# MOSFET_drivers.net
KiCad netlist of a schematic drawn in Altium Designer
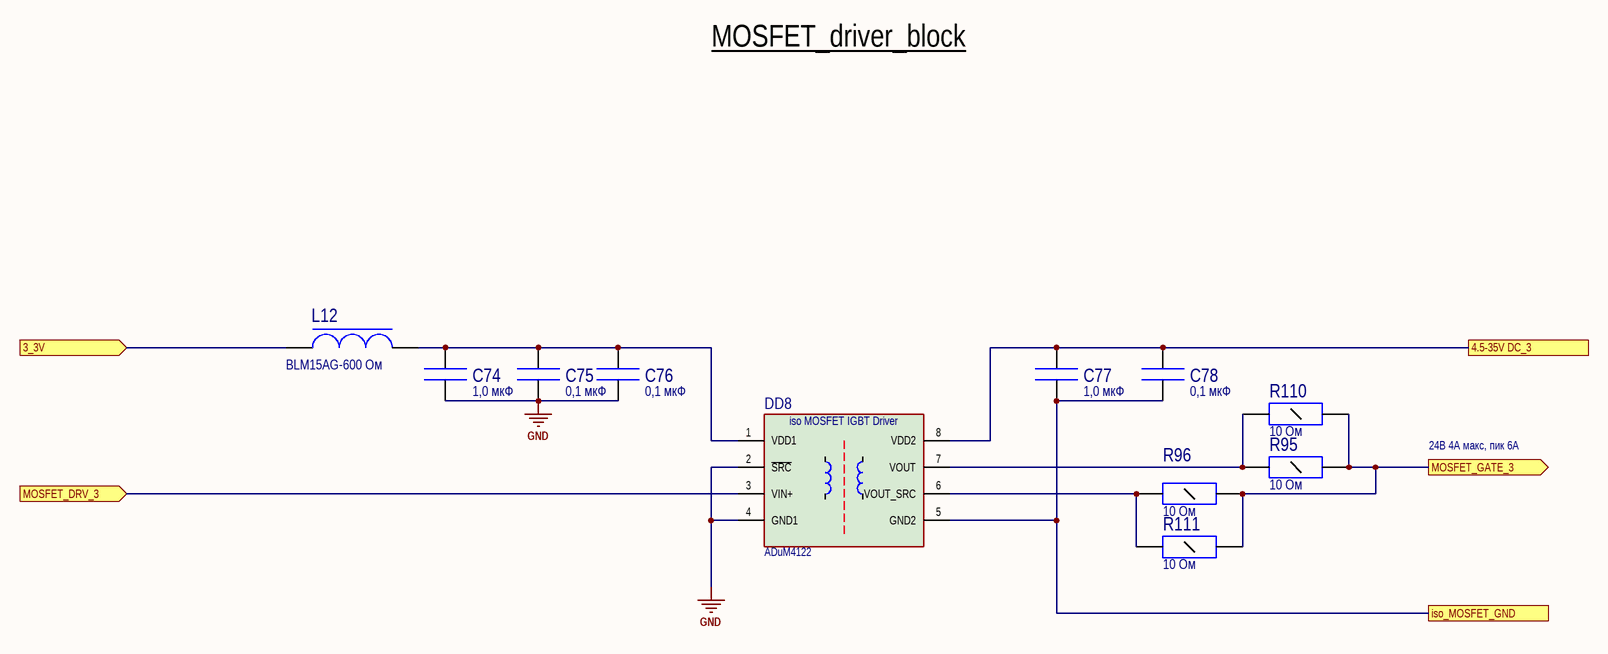
[diagram p0: MOSFET_drivers.SchDoc]

(export (version "E")
  (design (tool "Eeschema 10.0.6"))
  (components
    (comp (ref "C74")
      (value "1,0 мкФ")
      (footprint "CC1206")
      (description "Чип конденсатор керамический")
      (fields (field (name "Comment") "CC1206-X7R-1,0 мкФ-20%-50В"))
      (libsource (lib "Конденсаторы") (part "CC1206-X7R-#-20%-50В"))
    )
    (comp (ref "C75")
      (value "0,1 мкФ")
      (footprint "CC0603")
      (description "Чип конденсатор керамический")
      (fields (field (name "Comment") "CC0603-X7R-0,1 мкФ-20%-50В"))
      (libsource (lib "Конденсаторы") (part "CC0603-X7R-#-20%-50В"))
    )
    (comp (ref "C76")
      (value "0,1 мкФ")
      (footprint "CC0603")
      (description "Чип конденсатор керамический")
      (fields (field (name "Comment") "CC0603-X7R-0,1 мкФ-20%-50В"))
      (libsource (lib "Конденсаторы") (part "CC0603-X7R-#-20%-50В"))
    )
    (comp (ref "C77")
      (value "1,0 мкФ")
      (footprint "CC1206")
      (description "Чип конденсатор керамический")
      (fields (field (name "Comment") "CC1206-X7R-1,0 мкФ-20%-50В"))
      (libsource (lib "Конденсаторы") (part "CC1206-X7R-#-20%-50В"))
    )
    (comp (ref "C78")
      (value "0,1 мкФ")
      (footprint "CC0603")
      (description "Чип конденсатор керамический")
      (fields (field (name "Comment") "CC0603-X7R-0,1 мкФ-20%-50В"))
      (libsource (lib "Конденсаторы") (part "CC0603-X7R-#-20%-50В"))
    )
    (comp (ref "DD8")
      (value "ADuM4122")
      (footprint "SOIC127P1031X265-8N")
      (description "Single Gate, Adjustable Slew Rate, Isolated Gate Driver, 3 A Short-Circuit (<3Ω)")
      (libsource (lib "batmon_ICs") (part "ADuM4122ARIZ"))
    )
    (comp (ref "L12")
      (value "BLM15AG-600 Ом")
      (footprint "CL0402(1005)")
      (description "Чип индуктивность подавления EMP")
      (libsource (lib "Индуктивности") (part "BLM15"))
    )
    (comp (ref "R95")
      (value "10 Ом")
      (footprint "CR1206")
      (description "Чип резистор")
      (fields (field (name "Comment") "CR1206-10 Ом-±5%"))
      (libsource (lib "Резисторы") (part "CR1206-#-±5%"))
    )
    (comp (ref "R96")
      (value "10 Ом")
      (footprint "CR1206")
      (description "Чип резистор")
      (fields (field (name "Comment") "CR1206-10 Ом-±5%"))
      (libsource (lib "Резисторы") (part "CR1206-#-±5%"))
    )
    (comp (ref "R110")
      (value "10 Ом")
      (footprint "CR1206")
      (description "Чип резистор")
      (fields (field (name "Comment") "CR1206-10 Ом-±5%"))
      (libsource (lib "Резисторы") (part "CR1206-#-±5%"))
    )
    (comp (ref "R111")
      (value "10 Ом")
      (footprint "CR1206")
      (description "Чип резистор")
      (fields (field (name "Comment") "CR1206-10 Ом-±5%"))
      (libsource (lib "Резисторы") (part "CR1206-#-±5%"))
    )
  )
  (nets
    (net (code "1") (name "/3_3V") (class "Default")
      (node (ref "L12") (pin "1") (pinfunction "1_1") (pintype "passive"))
    )
    (net (code "2") (name "/4.5-35V DC_3") (class "Default")
      (node (ref "C77") (pin "1") (pinfunction "+_1") (pintype "passive"))
      (node (ref "C78") (pin "2") (pinfunction "-_2") (pintype "passive"))
      (node (ref "DD8") (pin "8") (pinfunction "VDD2_8") (pintype "power_in"))
    )
    (net (code "3") (name "/MOSFET_DRV_3") (class "Default")
      (node (ref "DD8") (pin "3") (pinfunction "VIN+_3") (pintype "passive"))
    )
    (net (code "4") (name "/MOSFET_GATE_3") (class "Default")
      (node (ref "R110") (pin "2") (pinfunction "-_2") (pintype "passive"))
      (node (ref "R111") (pin "2") (pinfunction "-_2") (pintype "passive"))
      (node (ref "R95") (pin "2") (pinfunction "-_2") (pintype "passive"))
      (node (ref "R96") (pin "2") (pinfunction "-_2") (pintype "passive"))
    )
    (net (code "5") (name "/iso_MOSFET_GND") (class "Default")
      (node (ref "C77") (pin "2") (pinfunction "-_2") (pintype "passive"))
      (node (ref "C78") (pin "1") (pinfunction "+_1") (pintype "passive"))
      (node (ref "DD8") (pin "5") (pinfunction "GND2_5") (pintype "power_in"))
    )
    (net (code "6") (name "GND") (class "Default")
      (node (ref "C74") (pin "2") (pinfunction "-_2") (pintype "passive"))
      (node (ref "C75") (pin "1") (pinfunction "+_1") (pintype "passive"))
      (node (ref "C76") (pin "1") (pinfunction "+_1") (pintype "passive"))
      (node (ref "DD8") (pin "2") (pinfunction "~{SRC}_2") (pintype "passive"))
      (node (ref "DD8") (pin "4") (pinfunction "GND1_4") (pintype "power_in"))
    )
    (net (code "7") (name "Net-(C74-+)") (class "Default")
      (node (ref "C74") (pin "1") (pinfunction "+_1") (pintype "passive"))
      (node (ref "C75") (pin "2") (pinfunction "-_2") (pintype "passive"))
      (node (ref "C76") (pin "2") (pinfunction "-_2") (pintype "passive"))
      (node (ref "DD8") (pin "1") (pinfunction "VDD1_1") (pintype "power_in"))
      (node (ref "L12") (pin "2") (pinfunction "2_2") (pintype "passive"))
    )
    (net (code "8") (name "Net-(DD8-VOUT)") (class "Default")
      (node (ref "DD8") (pin "7") (pinfunction "VOUT_7") (pintype "passive"))
      (node (ref "R110") (pin "1") (pinfunction "+_1") (pintype "passive"))
      (node (ref "R95") (pin "1") (pinfunction "+_1") (pintype "passive"))
    )
    (net (code "9") (name "Net-(DD8-VOUT_SRC)") (class "Default")
      (node (ref "DD8") (pin "6") (pinfunction "VOUT_SRC_6") (pintype "passive"))
      (node (ref "R111") (pin "1") (pinfunction "+_1") (pintype "passive"))
      (node (ref "R96") (pin "1") (pinfunction "+_1") (pintype "passive"))
    )
  )
)
